# Lync-presence-light.net
KiCad netlist of a schematic drawn in EAGLE
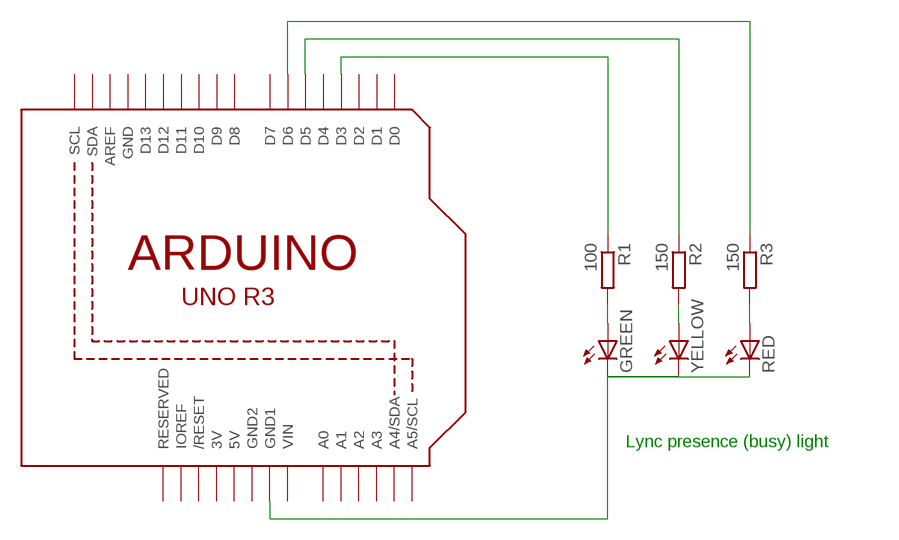
[diagram p0: schematic, sheet 1]

(export (version "E")
  (design (tool "Eeschema 10.0.6"))
  (components
    (comp (ref "GREEN")
      (value "LED5MM")
      (footprint "eagle-import:LED5MM")
      (libsource (lib "eagle-import") (part "LED5MM"))
    )
    (comp (ref "R1")
      (value "100")
      (footprint "eagle-import:0204_7")
      (libsource (lib "eagle-import") (part "R0204/7"))
    )
    (comp (ref "R2")
      (value "150")
      (footprint "eagle-import:0204_7")
      (libsource (lib "eagle-import") (part "R0204/7"))
    )
    (comp (ref "R3")
      (value "150")
      (footprint "eagle-import:0204_7")
      (libsource (lib "eagle-import") (part "R0204/7"))
    )
    (comp (ref "RED")
      (value "LED5MM")
      (footprint "eagle-import:LED5MM")
      (libsource (lib "eagle-import") (part "LED5MM"))
    )
    (comp (ref "U1")
      (value "ARDUINOR3-BPLACE")
      (footprint "eagle-import:ARDUINOR3-BPLACE")
      (libsource (lib "eagle-import") (part "ARDUINOR3-BPLACE"))
    )
    (comp (ref "YELLOW")
      (value "LED5MM")
      (footprint "eagle-import:LED5MM")
      (libsource (lib "eagle-import") (part "LED5MM"))
    )
  )
  (nets
    (net (code "1") (name "/3V") (class "Default")
      (node (ref "U1") (pin "3V") (pinfunction "3V_3V") (pintype "power_in"))
    )
    (net (code "2") (name "/5V") (class "Default")
      (node (ref "U1") (pin "5V") (pinfunction "5V_5V") (pintype "power_in"))
    )
    (net (code "3") (name "/GND") (class "Default")
      (node (ref "U1") (pin "GND") (pinfunction "GND_GND") (pintype "power_in"))
    )
    (net (code "4") (name "/GND2") (class "Default")
      (node (ref "U1") (pin "GND2") (pinfunction "GND2_GND2") (pintype "power_in"))
    )
    (net (code "5") (name "/VIN") (class "Default")
      (node (ref "U1") (pin "VIN") (pinfunction "VIN_VIN") (pintype "power_in"))
    )
    (net (code "6") (name "Net-(GREEN-C)") (class "Default")
      (node (ref "GREEN") (pin "K") (pinfunction "C_K") (pintype "passive"))
      (node (ref "RED") (pin "K") (pinfunction "C_K") (pintype "passive"))
      (node (ref "U1") (pin "GND1") (pinfunction "GND1_GND1") (pintype "power_in"))
      (node (ref "YELLOW") (pin "K") (pinfunction "C_K") (pintype "passive"))
    )
    (net (code "7") (name "Net-(GREEN-PadA)") (class "Default")
      (node (ref "GREEN") (pin "A") (pinfunction "A_A") (pintype "passive"))
      (node (ref "R1") (pin "2") (pinfunction "2_2") (pintype "passive"))
    )
    (net (code "8") (name "Net-(R1-Pad1)") (class "Default")
      (node (ref "R1") (pin "1") (pinfunction "1_1") (pintype "passive"))
      (node (ref "U1") (pin "D3") (pinfunction "D3_D3") (pintype "bidirectional"))
    )
    (net (code "9") (name "Net-(R2-Pad1)") (class "Default")
      (node (ref "R2") (pin "1") (pinfunction "1_1") (pintype "passive"))
      (node (ref "U1") (pin "D5") (pinfunction "D5_D5") (pintype "bidirectional"))
    )
    (net (code "10") (name "Net-(R2-Pad2)") (class "Default")
      (node (ref "R2") (pin "2") (pinfunction "2_2") (pintype "passive"))
      (node (ref "YELLOW") (pin "A") (pinfunction "A_A") (pintype "passive"))
    )
    (net (code "11") (name "Net-(R3-Pad1)") (class "Default")
      (node (ref "R3") (pin "1") (pinfunction "1_1") (pintype "passive"))
      (node (ref "U1") (pin "D6") (pinfunction "D6_D6") (pintype "bidirectional"))
    )
    (net (code "12") (name "Net-(R3-Pad2)") (class "Default")
      (node (ref "R3") (pin "2") (pinfunction "2_2") (pintype "passive"))
      (node (ref "RED") (pin "A") (pinfunction "A_A") (pintype "passive"))
    )
    (net (code "13") (name "unconnected-(U1-A4{slash}SDA-PadA4)") (class "Default")
      (node (ref "U1") (pin "A4") (pinfunction "A4/SDA_A4") (pintype "bidirectional"))
    )
    (net (code "14") (name "unconnected-(U1-A5{slash}SCL-PadA5)") (class "Default")
      (node (ref "U1") (pin "A5") (pinfunction "A5/SCL_A5") (pintype "bidirectional"))
    )
    (net (code "15") (name "unconnected-(U1-PadA0)") (class "Default")
      (node (ref "U1") (pin "A0") (pinfunction "A0_A0") (pintype "bidirectional"))
    )
    (net (code "16") (name "unconnected-(U1-PadA1)") (class "Default")
      (node (ref "U1") (pin "A1") (pinfunction "A1_A1") (pintype "bidirectional"))
    )
    (net (code "17") (name "unconnected-(U1-PadA2)") (class "Default")
      (node (ref "U1") (pin "A2") (pinfunction "A2_A2") (pintype "bidirectional"))
    )
    (net (code "18") (name "unconnected-(U1-PadA3)") (class "Default")
      (node (ref "U1") (pin "A3") (pinfunction "A3_A3") (pintype "bidirectional"))
    )
    (net (code "19") (name "unconnected-(U1-PadAREF)") (class "Default")
      (node (ref "U1") (pin "AREF") (pinfunction "AREF_AREF") (pintype "bidirectional"))
    )
    (net (code "20") (name "unconnected-(U1-PadD0)") (class "Default")
      (node (ref "U1") (pin "D0") (pinfunction "D0_D0") (pintype "bidirectional"))
    )
    (net (code "21") (name "unconnected-(U1-PadD1)") (class "Default")
      (node (ref "U1") (pin "D1") (pinfunction "D1_D1") (pintype "bidirectional"))
    )
    (net (code "22") (name "unconnected-(U1-PadD2)") (class "Default")
      (node (ref "U1") (pin "D2") (pinfunction "D2_D2") (pintype "bidirectional"))
    )
    (net (code "23") (name "unconnected-(U1-PadD4)") (class "Default")
      (node (ref "U1") (pin "D4") (pinfunction "D4_D4") (pintype "bidirectional"))
    )
    (net (code "24") (name "unconnected-(U1-PadD7)") (class "Default")
      (node (ref "U1") (pin "D7") (pinfunction "D7_D7") (pintype "bidirectional"))
    )
    (net (code "25") (name "unconnected-(U1-PadD8)") (class "Default")
      (node (ref "U1") (pin "D8") (pinfunction "D8_D8") (pintype "bidirectional"))
    )
    (net (code "26") (name "unconnected-(U1-PadD9)") (class "Default")
      (node (ref "U1") (pin "D9") (pinfunction "D9_D9") (pintype "bidirectional"))
    )
    (net (code "27") (name "unconnected-(U1-PadD10)") (class "Default")
      (node (ref "U1") (pin "D10") (pinfunction "D10_D10") (pintype "bidirectional"))
    )
    (net (code "28") (name "unconnected-(U1-PadD11)") (class "Default")
      (node (ref "U1") (pin "D11") (pinfunction "D11_D11") (pintype "bidirectional"))
    )
    (net (code "29") (name "unconnected-(U1-PadD12)") (class "Default")
      (node (ref "U1") (pin "D12") (pinfunction "D12_D12") (pintype "bidirectional"))
    )
    (net (code "30") (name "unconnected-(U1-PadD13)") (class "Default")
      (node (ref "U1") (pin "D13") (pinfunction "D13_D13") (pintype "bidirectional"))
    )
    (net (code "31") (name "unconnected-(U1-PadIOREF)") (class "Default")
      (node (ref "U1") (pin "IOREF") (pinfunction "IOREF_IOREF") (pintype "output"))
    )
    (net (code "32") (name "unconnected-(U1-PadRESERVED)") (class "Default")
      (node (ref "U1") (pin "RESERVED") (pinfunction "RESERVED_RESERVED") (pintype "no_connect"))
    )
    (net (code "33") (name "unconnected-(U1-PadSCL)") (class "Default")
      (node (ref "U1") (pin "SCL") (pinfunction "SCL_SCL") (pintype "bidirectional"))
    )
    (net (code "34") (name "unconnected-(U1-PadSDA)") (class "Default")
      (node (ref "U1") (pin "SDA") (pinfunction "SDA_SDA") (pintype "bidirectional"))
    )
    (net (code "35") (name "unconnected-(U1-{slash}RESET-PadRESET)") (class "Default")
      (node (ref "U1") (pin "RESET") (pinfunction "/RESET_RESET") (pintype "bidirectional"))
    )
  )
)
